# DIDV_-_Buck.net
KiCad netlist of a schematic drawn in EAGLE
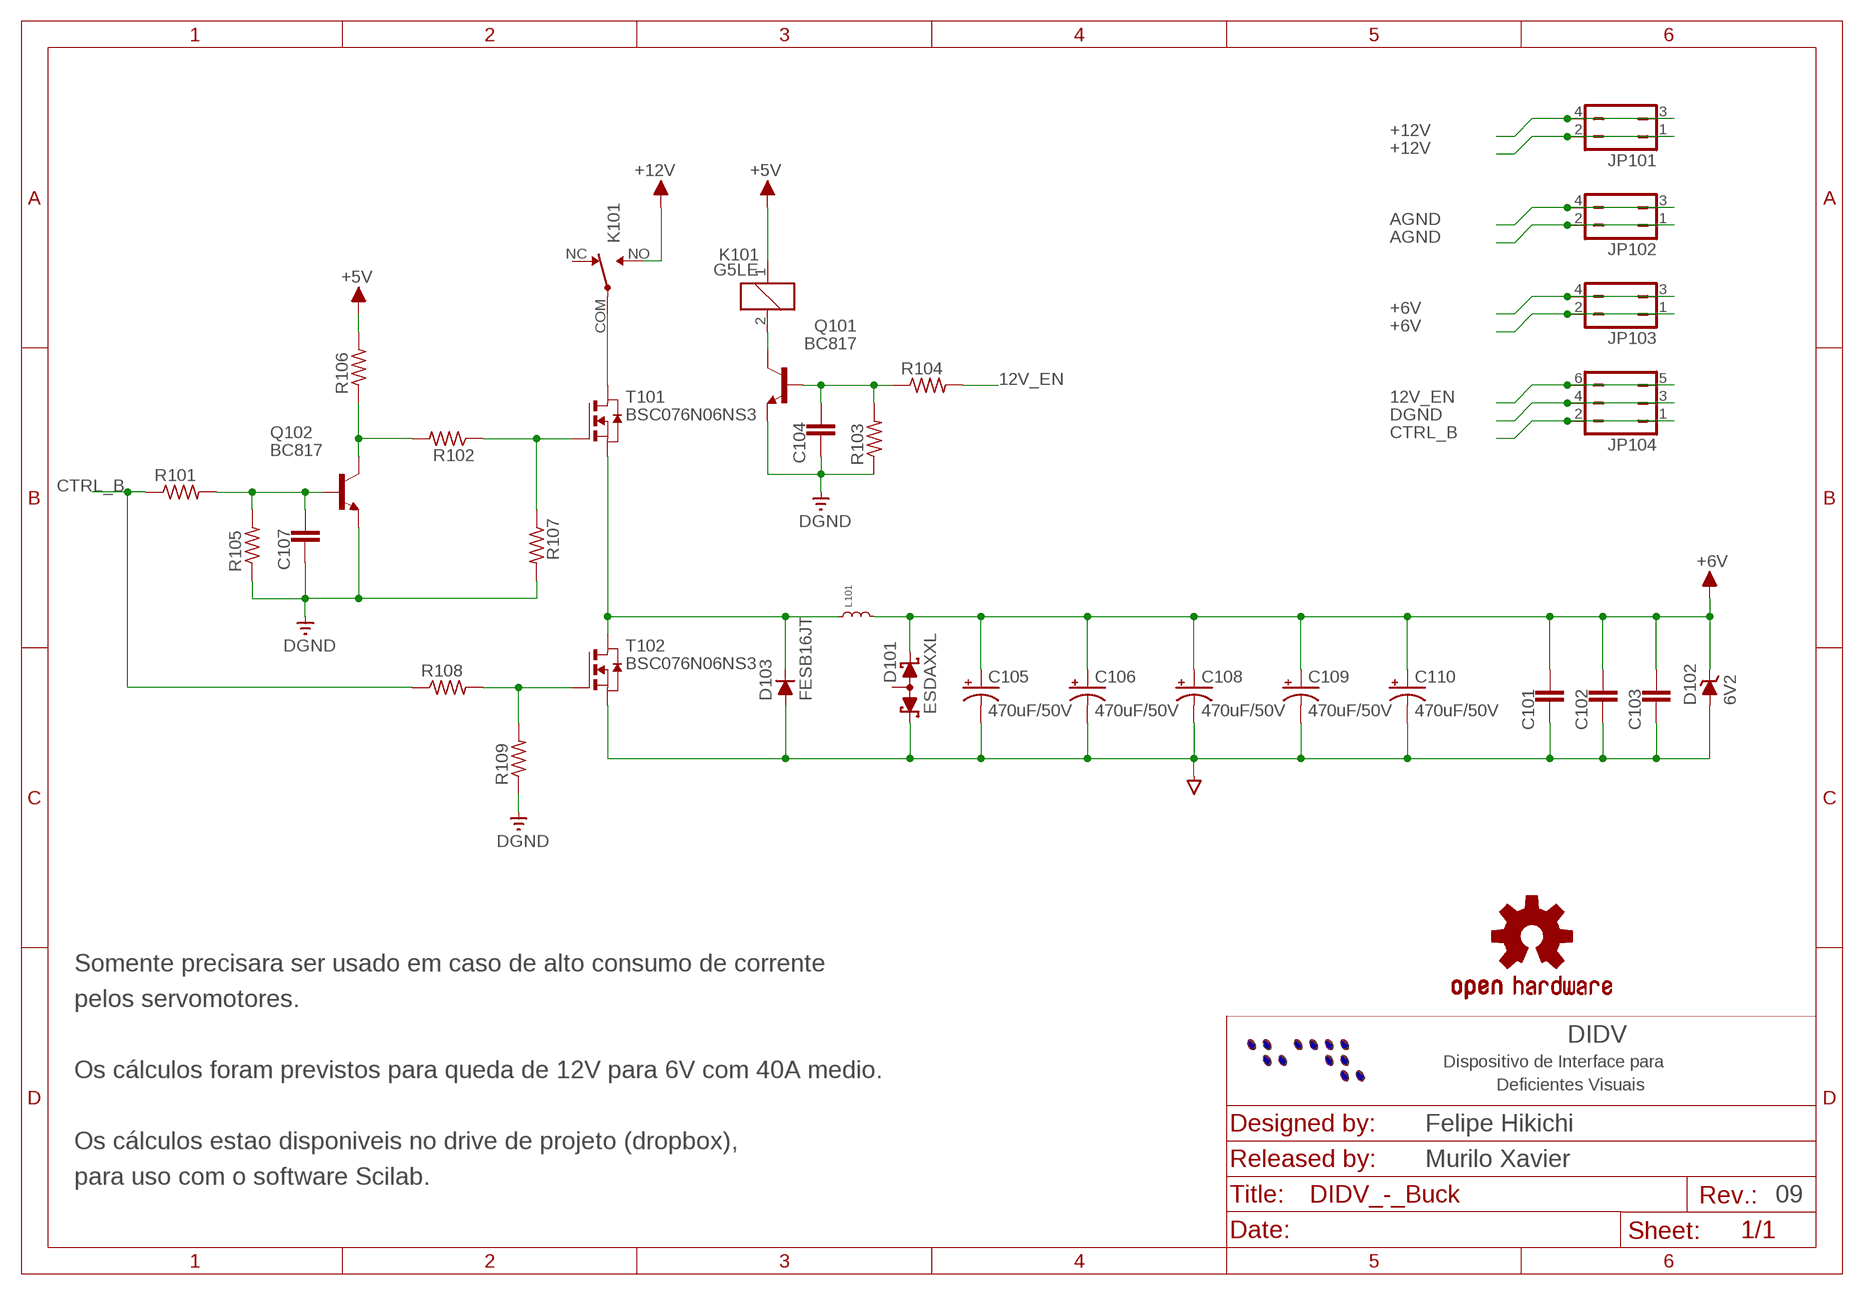
[diagram p0: schematic, sheet 1]

(export (version "E")
  (design (tool "Eeschema 10.0.6"))
  (components
    (comp (ref "C101")
      (value "C-EUC0805")
      (footprint "eagle-import:C0805")
      (libsource (lib "eagle-import") (part "C-EUC0805"))
    )
    (comp (ref "C102")
      (value "C-EUC0805")
      (footprint "eagle-import:C0805")
      (libsource (lib "eagle-import") (part "C-EUC0805"))
    )
    (comp (ref "C103")
      (value "C-EUC0805")
      (footprint "eagle-import:C0805")
      (libsource (lib "eagle-import") (part "C-EUC0805"))
    )
    (comp (ref "C104")
      (value "C-EUC0603")
      (footprint "eagle-import:C0603")
      (libsource (lib "eagle-import") (part "C-EUC0603"))
    )
    (comp (ref "C105")
      (value "470uF/50V")
      (footprint "eagle-import:E5-13")
      (libsource (lib "eagle-import") (part "CPOL-USE5-13"))
    )
    (comp (ref "C106")
      (value "470uF/50V")
      (footprint "eagle-import:E5-13")
      (libsource (lib "eagle-import") (part "CPOL-USE5-13"))
    )
    (comp (ref "C107")
      (value "C-EUC0603")
      (footprint "eagle-import:C0603")
      (libsource (lib "eagle-import") (part "C-EUC0603"))
    )
    (comp (ref "C108")
      (value "470uF/50V")
      (footprint "eagle-import:E5-13")
      (libsource (lib "eagle-import") (part "CPOL-USE5-13"))
    )
    (comp (ref "C109")
      (value "470uF/50V")
      (footprint "eagle-import:E5-13")
      (libsource (lib "eagle-import") (part "CPOL-USE5-13"))
    )
    (comp (ref "C110")
      (value "470uF/50V")
      (footprint "eagle-import:E5-13")
      (libsource (lib "eagle-import") (part "CPOL-USE5-13"))
    )
    (comp (ref "D101")
      (value "ESDAXXL")
      (footprint "eagle-import:SOT23")
      (libsource (lib "eagle-import") (part "ESDAXXL"))
    )
    (comp (ref "D102")
      (value "6V2")
      (footprint "eagle-import:SOT23")
      (libsource (lib "eagle-import") (part "BZX84"))
    )
    (comp (ref "D103")
      (value "FESB16JT")
      (footprint "eagle-import:D2PAK")
      (libsource (lib "eagle-import") (part "MBRB745PBF"))
    )
    (comp (ref "JP101")
      (value "JP2QM")
      (footprint "eagle-import:JP2QM")
      (libsource (lib "eagle-import") (part "JP2QM"))
    )
    (comp (ref "JP102")
      (value "JP2QM")
      (footprint "eagle-import:JP2QM")
      (libsource (lib "eagle-import") (part "JP2QM"))
    )
    (comp (ref "JP103")
      (value "JP2QM")
      (footprint "eagle-import:JP2QM")
      (libsource (lib "eagle-import") (part "JP2QM"))
    )
    (comp (ref "JP104")
      (value "JP3QM")
      (footprint "eagle-import:JP3QM")
      (libsource (lib "eagle-import") (part "JP3QM"))
    )
    (comp (ref "K101")
      (value "G5LE")
      (footprint "eagle-import:G5LE")
      (libsource (lib "eagle-import") (part "G5LE"))
    )
    (comp (ref "L101")
      (value "INDUCTOR")
      (footprint "eagle-import:SER2918H-682KL")
      (libsource (lib "eagle-import") (part "INDUCTOR"))
    )
    (comp (ref "LOGO101")
      (value "OSHW-LOGOL")
      (footprint "eagle-import:OSHW-LOGO-L")
      (libsource (lib "eagle-import") (part "OSHW-LOGOL"))
    )
    (comp (ref "Q101")
      (value "BC817")
      (footprint "eagle-import:SOT23-BEC")
      (libsource (lib "eagle-import") (part "-NPN-SOT23-BECBC817-16"))
    )
    (comp (ref "Q102")
      (value "BC817")
      (footprint "eagle-import:SOT23-BEC")
      (libsource (lib "eagle-import") (part "-NPN-SOT23-BECBC817-16"))
    )
    (comp (ref "R101")
      (value "R-US_R0603")
      (footprint "eagle-import:R0603")
      (libsource (lib "eagle-import") (part "R-US_R0603"))
    )
    (comp (ref "R102")
      (value "R-US_R0805")
      (footprint "eagle-import:R0805")
      (libsource (lib "eagle-import") (part "R-US_R0805"))
    )
    (comp (ref "R103")
      (value "R-US_R0603")
      (footprint "eagle-import:R0603")
      (libsource (lib "eagle-import") (part "R-US_R0603"))
    )
    (comp (ref "R104")
      (value "R-US_R0603")
      (footprint "eagle-import:R0603")
      (libsource (lib "eagle-import") (part "R-US_R0603"))
    )
    (comp (ref "R105")
      (value "R-US_R0603")
      (footprint "eagle-import:R0603")
      (libsource (lib "eagle-import") (part "R-US_R0603"))
    )
    (comp (ref "R106")
      (value "R-US_R0805")
      (footprint "eagle-import:R0805")
      (libsource (lib "eagle-import") (part "R-US_R0805"))
    )
    (comp (ref "R107")
      (value "R-US_R0805")
      (footprint "eagle-import:R0805")
      (libsource (lib "eagle-import") (part "R-US_R0805"))
    )
    (comp (ref "R108")
      (value "R-US_R0805")
      (footprint "eagle-import:R0805")
      (libsource (lib "eagle-import") (part "R-US_R0805"))
    )
    (comp (ref "R109")
      (value "R-US_R0805")
      (footprint "eagle-import:R0805")
      (libsource (lib "eagle-import") (part "R-US_R0805"))
    )
    (comp (ref "T101")
      (value "BSC076N06NS3")
      (footprint "eagle-import:PG-TDSON-8")
      (libsource (lib "eagle-import") (part "BSC067N06LS3_G_PG-TDSON-8"))
    )
    (comp (ref "T102")
      (value "BSC076N06NS3")
      (footprint "eagle-import:PG-TDSON-8")
      (libsource (lib "eagle-import") (part "BSC067N06LS3_G_PG-TDSON-8"))
    )
  )
  (nets
    (net (code "1") (name "+5V") (class "Default")
      (node (ref "K101") (pin "1") (pinfunction "1_1") (pintype "passive"))
      (node (ref "R106") (pin "2") (pinfunction "2_2") (pintype "passive"))
    )
    (net (code "2") (name "+6V") (class "Default")
      (node (ref "C101") (pin "1") (pinfunction "1_1") (pintype "passive"))
      (node (ref "C102") (pin "1") (pinfunction "1_1") (pintype "passive"))
      (node (ref "C103") (pin "1") (pinfunction "1_1") (pintype "passive"))
      (node (ref "C105") (pin "+") (pinfunction "+_+") (pintype "passive"))
      (node (ref "C106") (pin "+") (pinfunction "+_+") (pintype "passive"))
      (node (ref "C108") (pin "+") (pinfunction "+_+") (pintype "passive"))
      (node (ref "C109") (pin "+") (pinfunction "+_+") (pintype "passive"))
      (node (ref "C110") (pin "+") (pinfunction "+_+") (pintype "passive"))
      (node (ref "D101") (pin "2") (pinfunction "C2_2") (pintype "passive"))
      (node (ref "D102") (pin "3") (pinfunction "C_3") (pintype "passive"))
      (node (ref "JP103") (pin "1") (pinfunction "1_1") (pintype "passive"))
      (node (ref "JP103") (pin "2") (pinfunction "2_2") (pintype "passive"))
      (node (ref "JP103") (pin "3") (pinfunction "3_3") (pintype "passive"))
      (node (ref "JP103") (pin "4") (pinfunction "4_4") (pintype "passive"))
      (node (ref "L101") (pin "2") (pinfunction "2_2") (pintype "passive"))
    )
    (net (code "3") (name "+12V") (class "Default")
      (node (ref "JP101") (pin "1") (pinfunction "1_1") (pintype "passive"))
      (node (ref "JP101") (pin "2") (pinfunction "2_2") (pintype "passive"))
      (node (ref "JP101") (pin "3") (pinfunction "3_3") (pintype "passive"))
      (node (ref "JP101") (pin "4") (pinfunction "4_4") (pintype "passive"))
      (node (ref "K101") (pin "NO") (pinfunction "NO_NO") (pintype "passive"))
    )
    (net (code "4") (name "/12V_EN") (class "Default")
      (node (ref "JP104") (pin "5") (pinfunction "5_5") (pintype "passive"))
      (node (ref "JP104") (pin "6") (pinfunction "6_6") (pintype "passive"))
      (node (ref "R104") (pin "2") (pinfunction "2_2") (pintype "passive"))
    )
    (net (code "5") (name "/CTRL_B") (class "Default")
      (node (ref "JP104") (pin "1") (pinfunction "1_1") (pintype "passive"))
      (node (ref "JP104") (pin "2") (pinfunction "2_2") (pintype "passive"))
      (node (ref "R101") (pin "1") (pinfunction "1_1") (pintype "passive"))
      (node (ref "R108") (pin "1") (pinfunction "1_1") (pintype "passive"))
    )
    (net (code "6") (name "AGND") (class "Default")
      (node (ref "C101") (pin "2") (pinfunction "2_2") (pintype "passive"))
      (node (ref "C102") (pin "2") (pinfunction "2_2") (pintype "passive"))
      (node (ref "C103") (pin "2") (pinfunction "2_2") (pintype "passive"))
      (node (ref "C105") (pin "-") (pinfunction "-_-") (pintype "passive"))
      (node (ref "C106") (pin "-") (pinfunction "-_-") (pintype "passive"))
      (node (ref "C108") (pin "-") (pinfunction "-_-") (pintype "passive"))
      (node (ref "C109") (pin "-") (pinfunction "-_-") (pintype "passive"))
      (node (ref "C110") (pin "-") (pinfunction "-_-") (pintype "passive"))
      (node (ref "D101") (pin "1") (pinfunction "C1_1") (pintype "passive"))
      (node (ref "D102") (pin "1") (pinfunction "A_1") (pintype "passive"))
      (node (ref "D103") (pin "3") (pinfunction "A_3") (pintype "passive"))
      (node (ref "JP102") (pin "1") (pinfunction "1_1") (pintype "passive"))
      (node (ref "JP102") (pin "2") (pinfunction "2_2") (pintype "passive"))
      (node (ref "JP102") (pin "3") (pinfunction "3_3") (pintype "passive"))
      (node (ref "JP102") (pin "4") (pinfunction "4_4") (pintype "passive"))
      (node (ref "T102") (pin "1") (pinfunction "S_1") (pintype "passive"))
      (node (ref "T102") (pin "2") (pinfunction "S_2") (pintype "passive"))
      (node (ref "T102") (pin "3") (pinfunction "S_3") (pintype "passive"))
    )
    (net (code "7") (name "DGND") (class "Default")
      (node (ref "C104") (pin "2") (pinfunction "2_2") (pintype "passive"))
      (node (ref "C107") (pin "2") (pinfunction "2_2") (pintype "passive"))
      (node (ref "JP104") (pin "3") (pinfunction "3_3") (pintype "passive"))
      (node (ref "JP104") (pin "4") (pinfunction "4_4") (pintype "passive"))
      (node (ref "Q101") (pin "E") (pinfunction "E_E") (pintype "passive"))
      (node (ref "Q102") (pin "E") (pinfunction "E_E") (pintype "passive"))
      (node (ref "R103") (pin "1") (pinfunction "1_1") (pintype "passive"))
      (node (ref "R105") (pin "1") (pinfunction "1_1") (pintype "passive"))
      (node (ref "R107") (pin "2") (pinfunction "2_2") (pintype "passive"))
      (node (ref "R109") (pin "1") (pinfunction "1_1") (pintype "passive"))
    )
    (net (code "8") (name "Net-(C104-Pad1)") (class "Default")
      (node (ref "C104") (pin "1") (pinfunction "1_1") (pintype "passive"))
      (node (ref "Q101") (pin "B") (pinfunction "B_B") (pintype "passive"))
      (node (ref "R103") (pin "2") (pinfunction "2_2") (pintype "passive"))
      (node (ref "R104") (pin "1") (pinfunction "1_1") (pintype "passive"))
    )
    (net (code "9") (name "Net-(C107-Pad1)") (class "Default")
      (node (ref "C107") (pin "1") (pinfunction "1_1") (pintype "passive"))
      (node (ref "Q102") (pin "B") (pinfunction "B_B") (pintype "passive"))
      (node (ref "R101") (pin "2") (pinfunction "2_2") (pintype "passive"))
      (node (ref "R105") (pin "2") (pinfunction "2_2") (pintype "passive"))
    )
    (net (code "10") (name "Net-(D103-C-Pad1)") (class "Default")
      (node (ref "D103") (pin "1") (pinfunction "C_1") (pintype "passive"))
      (node (ref "D103") (pin "2") (pinfunction "C_2") (pintype "passive"))
      (node (ref "L101") (pin "1") (pinfunction "1_1") (pintype "passive"))
      (node (ref "T101") (pin "1") (pinfunction "S_1") (pintype "passive"))
      (node (ref "T101") (pin "2") (pinfunction "S_2") (pintype "passive"))
      (node (ref "T101") (pin "3") (pinfunction "S_3") (pintype "passive"))
      (node (ref "T102") (pin "5") (pinfunction "D_5") (pintype "passive"))
      (node (ref "T102") (pin "6") (pinfunction "D_6") (pintype "passive"))
      (node (ref "T102") (pin "7") (pinfunction "D_7") (pintype "passive"))
      (node (ref "T102") (pin "8") (pinfunction "D_8") (pintype "passive"))
      (node (ref "T102") (pin "D") (pinfunction "D_D") (pintype "passive"))
    )
    (net (code "11") (name "Net-(K101-Pad2)") (class "Default")
      (node (ref "K101") (pin "2") (pinfunction "2_2") (pintype "passive"))
      (node (ref "Q101") (pin "C") (pinfunction "C_C") (pintype "passive"))
    )
    (net (code "12") (name "Net-(K101-PadCOM)") (class "Default")
      (node (ref "K101") (pin "COM") (pinfunction "COM_COM") (pintype "passive"))
      (node (ref "T101") (pin "5") (pinfunction "D_5") (pintype "passive"))
      (node (ref "T101") (pin "6") (pinfunction "D_6") (pintype "passive"))
      (node (ref "T101") (pin "7") (pinfunction "D_7") (pintype "passive"))
      (node (ref "T101") (pin "8") (pinfunction "D_8") (pintype "passive"))
      (node (ref "T101") (pin "D") (pinfunction "D_D") (pintype "passive"))
    )
    (net (code "13") (name "Net-(Q102-PadC)") (class "Default")
      (node (ref "Q102") (pin "C") (pinfunction "C_C") (pintype "passive"))
      (node (ref "R102") (pin "2") (pinfunction "2_2") (pintype "passive"))
      (node (ref "R106") (pin "1") (pinfunction "1_1") (pintype "passive"))
    )
    (net (code "14") (name "Net-(T101-G)") (class "Default")
      (node (ref "R102") (pin "1") (pinfunction "1_1") (pintype "passive"))
      (node (ref "R107") (pin "1") (pinfunction "1_1") (pintype "passive"))
      (node (ref "T101") (pin "4") (pinfunction "G_4") (pintype "passive"))
    )
    (net (code "15") (name "Net-(T102-G)") (class "Default")
      (node (ref "R108") (pin "2") (pinfunction "2_2") (pintype "passive"))
      (node (ref "R109") (pin "2") (pinfunction "2_2") (pintype "passive"))
      (node (ref "T102") (pin "4") (pinfunction "G_4") (pintype "passive"))
    )
    (net (code "16") (name "unconnected-(D101-A-Pad3)") (class "Default")
      (node (ref "D101") (pin "3") (pinfunction "A_3") (pintype "passive"))
    )
    (net (code "17") (name "unconnected-(K101-PadNC)") (class "Default")
      (node (ref "K101") (pin "NC") (pinfunction "NC_NC") (pintype "passive"))
    )
  )
)
